# 18F4520SCH_-_Copy.net
KiCad netlist of a schematic drawn in Altium Designer
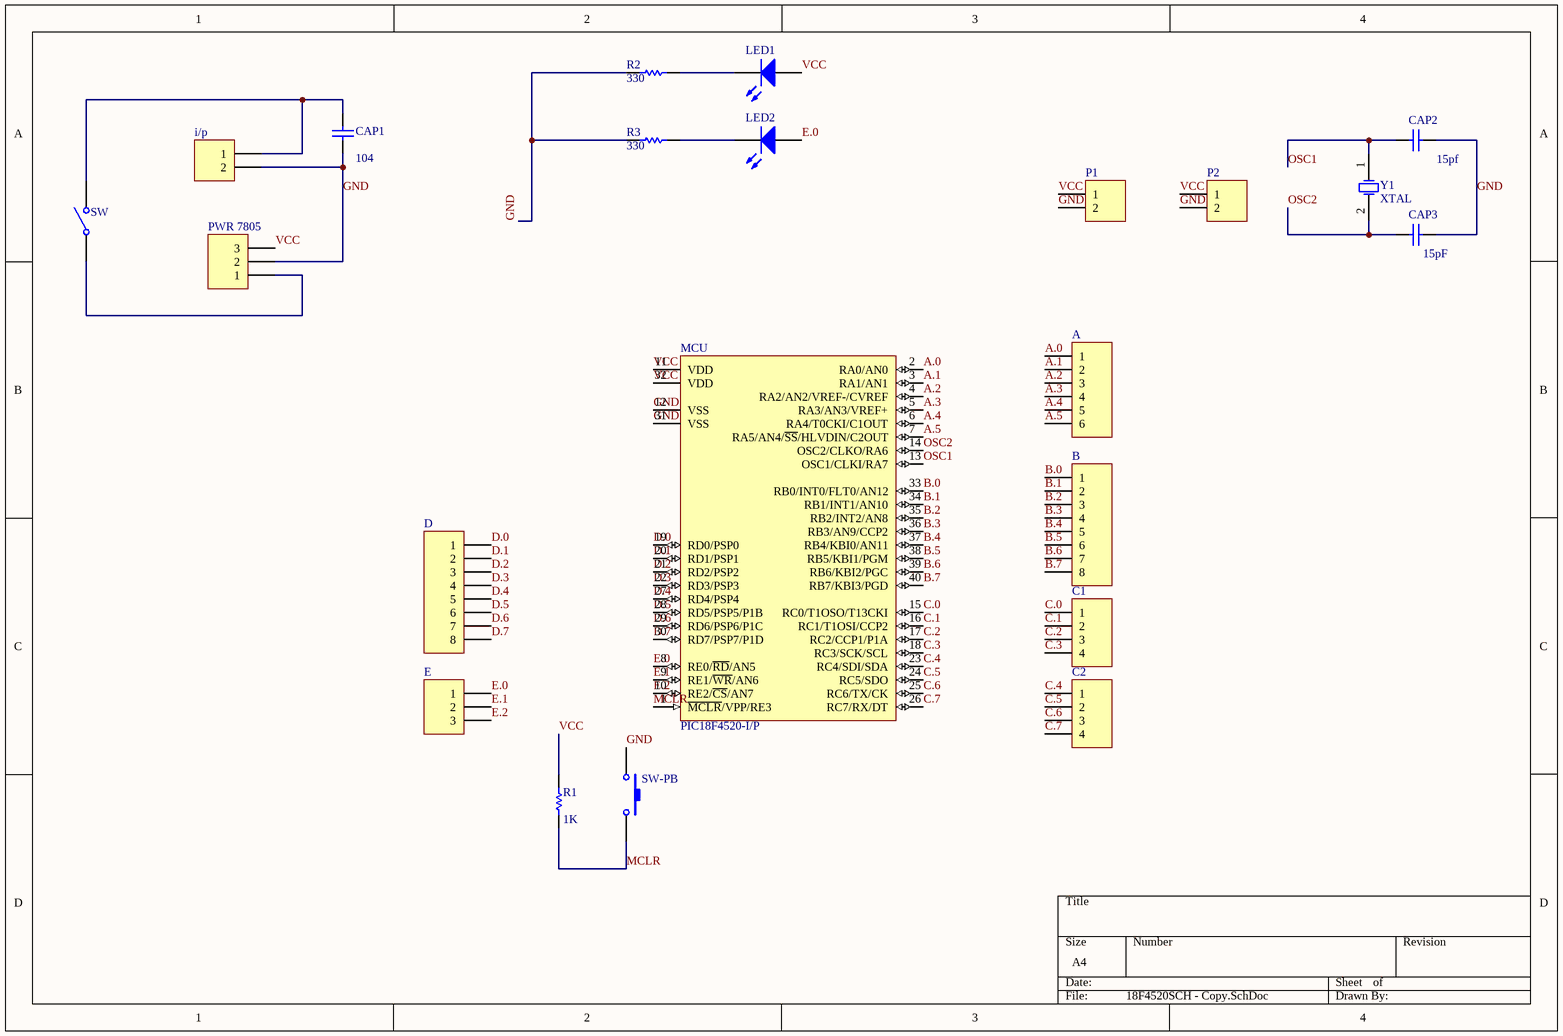
[diagram p0: 18F4520SCH - Copy.SchDoc]

(export (version "E")
  (design (tool "Eeschema 10.0.6"))
  (components
    (comp (ref "A")
      (value "Header 6")
      (footprint "HDR1X6")
      (description "Header, 6-Pin")
      (fields (field (name "PUBLISHER") "Altium Limited"))
      (libsource (lib "Miscellaneous Connectors") (part "Header 6"))
    )
    (comp (ref "B")
      (value "Header 8")
      (footprint "HDR1X8")
      (description "Header, 8-Pin")
      (fields (field (name "PUBLISHER") "Altium Limited"))
      (libsource (lib "") (part "Header 8_1"))
    )
    (comp (ref "C1")
      (value "Header 4")
      (footprint "HDR1X4")
      (description "Header, 4-Pin")
      (fields (field (name "PUBLISHER") "Altium Limited"))
      (libsource (lib "Miscellaneous Connectors") (part "Header 4"))
    )
    (comp (ref "C2")
      (value "Header 4")
      (footprint "HDR1X4")
      (description "Header, 4-Pin")
      (fields (field (name "PUBLISHER") "Altium Limited"))
      (libsource (lib "Miscellaneous Connectors") (part "Header 4"))
    )
    (comp (ref "CAP1")
      (value "104")
      (footprint "Miscellaneous Connectors:HDR1X2")
      (description "Capacitor")
      (fields (field (name "Comment") "Cap") (field (name "PUBLISHER") "Altium Limited"))
      (libsource (lib "Miscellaneous Devices") (part "Cap"))
    )
    (comp (ref "CAP2")
      (value "15pf")
      (footprint "Miscellaneous Connectors:HDR1X2")
      (description "Capacitor")
      (fields (field (name "Comment") "Cap") (field (name "PUBLISHER") "Altium Limited"))
      (libsource (lib "Miscellaneous Devices") (part "Cap"))
    )
    (comp (ref "CAP3")
      (value "15pF")
      (footprint "Miscellaneous Connectors:HDR1X2")
      (description "Capacitor")
      (fields (field (name "Comment") "Cap") (field (name "PUBLISHER") "Altium Limited"))
      (libsource (lib "Miscellaneous Devices") (part "Cap"))
    )
    (comp (ref "D")
      (value "Header 8")
      (footprint "HDR1X8")
      (description "Header, 8-Pin")
      (fields (field (name "PUBLISHER") "Altium Limited"))
      (libsource (lib "Miscellaneous Connectors") (part "Header 8"))
    )
    (comp (ref "E")
      (value "Header 3")
      (footprint "HDR1X3")
      (description "Header, 3-Pin")
      (fields (field (name "PUBLISHER") "Altium Limited"))
      (libsource (lib "Miscellaneous Connectors") (part "Header 3"))
    )
    (comp (ref "i/p")
      (value "Header 2")
      (footprint "HDR1X2")
      (description "Header, 2-Pin")
      (fields (field (name "PUBLISHER") "Altium Limited"))
      (libsource (lib "Miscellaneous Connectors") (part "Header 2"))
    )
    (comp (ref "LED1")
      (value "LED2")
      (footprint "Miscellaneous Connectors:HDR1X2")
      (description "Typical RED, GREEN, YELLOW, AMBER GaAs LED")
      (fields (field (name "PUBLISHER") "Altium Limited"))
      (libsource (lib "Miscellaneous Devices") (part "LED2"))
    )
    (comp (ref "LED2")
      (value "LED2")
      (footprint "Miscellaneous Connectors:HDR1X2")
      (description "Typical RED, GREEN, YELLOW, AMBER GaAs LED")
      (fields (field (name "PUBLISHER") "Altium Limited"))
      (libsource (lib "Miscellaneous Devices") (part "LED2"))
    )
    (comp (ref "MCU")
      (value "PIC18F4520-I/P")
      (footprint "Microchip Microcontroller 8-Bit PIC16:PDIP600-P40")
      (fields (field (name "PUBLISHER") "Altium Limited"))
      (libsource (lib "Microchip Microcontroller 8-Bit PIC18") (part "PIC18F4520-I/P"))
    )
    (comp (ref "P1")
      (value "Header 2")
      (footprint "HDR1X2")
      (description "Header, 2-Pin")
      (fields (field (name "PUBLISHER") "Altium Limited"))
      (libsource (lib "") (part "Header 2_1"))
    )
    (comp (ref "P2")
      (value "Header 2")
      (footprint "HDR1X2")
      (description "Header, 2-Pin")
      (fields (field (name "PUBLISHER") "Altium Limited"))
      (libsource (lib "") (part "Header 2_1"))
    )
    (comp (ref "PWR 7805")
      (value "Header 3")
      (footprint "HDR1X3")
      (description "Header, 3-Pin")
      (fields (field (name "PUBLISHER") "Altium Limited"))
      (libsource (lib "") (part "Header 3_1"))
    )
    (comp (ref "R1")
      (value "1K")
      (footprint "AXIAL-0.3")
      (description "Resistor")
      (fields (field (name "Comment") "Res1") (field (name "PUBLISHER") "Altium Limited"))
      (libsource (lib "Miscellaneous Devices") (part "Res1"))
    )
    (comp (ref "R2")
      (value "330")
      (footprint "AXIAL-0.3")
      (description "Resistor")
      (fields (field (name "Comment") "Res1") (field (name "PUBLISHER") "Altium Limited"))
      (libsource (lib "Miscellaneous Devices") (part "Res1"))
    )
    (comp (ref "R3")
      (value "330")
      (footprint "AXIAL-0.3")
      (description "Resistor")
      (fields (field (name "Comment") "Res1") (field (name "PUBLISHER") "Altium Limited"))
      (libsource (lib "Miscellaneous Devices") (part "Res1"))
    )
    (comp (ref "SW")
      (value "SW-SPST")
      (footprint "SPST-2")
      (description "Single-Pole, Single-Throw Switch")
      (fields (field (name "PUBLISHER") "Altium Limited"))
      (libsource (lib "Miscellaneous Devices") (part "SW-SPST"))
    )
    (comp (ref "SW-PB")
      (value "SW-PB")
      (footprint "SPST-2")
      (description "Switch")
      (fields (field (name "PUBLISHER") "Altium Limited"))
      (libsource (lib "Miscellaneous Devices") (part "SW-PB"))
    )
    (comp (ref "Y1")
      (value "XTAL")
      (footprint "R38")
      (description "Crystal Oscillator")
      (fields (field (name "PUBLISHER") "Altium Limited"))
      (libsource (lib "Miscellaneous Devices") (part "XTAL"))
    )
  )
  (nets
    (net (code "1") (name "/A.0") (class "Default")
      (node (ref "A") (pin "1") (pinfunction "1_1") (pintype "passive"))
      (node (ref "MCU") (pin "2") (pinfunction "RA0/AN0_2") (pintype "bidirectional"))
    )
    (net (code "2") (name "/A.1") (class "Default")
      (node (ref "A") (pin "2") (pinfunction "2_2") (pintype "passive"))
      (node (ref "MCU") (pin "3") (pinfunction "RA1/AN1_3") (pintype "bidirectional"))
    )
    (net (code "3") (name "/A.2") (class "Default")
      (node (ref "A") (pin "3") (pinfunction "3_3") (pintype "passive"))
      (node (ref "MCU") (pin "4") (pinfunction "RA2/AN2/VREF-/CVREF_4") (pintype "bidirectional"))
    )
    (net (code "4") (name "/A.3") (class "Default")
      (node (ref "A") (pin "4") (pinfunction "4_4") (pintype "passive"))
      (node (ref "MCU") (pin "5") (pinfunction "RA3/AN3/VREF+_5") (pintype "bidirectional"))
    )
    (net (code "5") (name "/A.4") (class "Default")
      (node (ref "A") (pin "5") (pinfunction "5_5") (pintype "passive"))
      (node (ref "MCU") (pin "6") (pinfunction "RA4/T0CKI/C1OUT_6") (pintype "bidirectional"))
    )
    (net (code "6") (name "/A.5") (class "Default")
      (node (ref "A") (pin "6") (pinfunction "6_6") (pintype "passive"))
      (node (ref "MCU") (pin "7") (pinfunction "RA5/AN4/~{SS}/HLVDIN/C2OUT_7") (pintype "bidirectional"))
    )
    (net (code "7") (name "/B.0") (class "Default")
      (node (ref "B") (pin "1") (pinfunction "1_1") (pintype "passive"))
      (node (ref "MCU") (pin "33") (pinfunction "RB0/INT0/FLT0/AN12_33") (pintype "bidirectional"))
    )
    (net (code "8") (name "/B.1") (class "Default")
      (node (ref "B") (pin "2") (pinfunction "2_2") (pintype "passive"))
      (node (ref "MCU") (pin "34") (pinfunction "RB1/INT1/AN10_34") (pintype "bidirectional"))
    )
    (net (code "9") (name "/B.2") (class "Default")
      (node (ref "B") (pin "3") (pinfunction "3_3") (pintype "passive"))
      (node (ref "MCU") (pin "35") (pinfunction "RB2/INT2/AN8_35") (pintype "bidirectional"))
    )
    (net (code "10") (name "/B.3") (class "Default")
      (node (ref "B") (pin "4") (pinfunction "4_4") (pintype "passive"))
      (node (ref "MCU") (pin "36") (pinfunction "RB3/AN9/CCP2_36") (pintype "bidirectional"))
    )
    (net (code "11") (name "/B.4") (class "Default")
      (node (ref "B") (pin "5") (pinfunction "5_5") (pintype "passive"))
      (node (ref "MCU") (pin "37") (pinfunction "RB4/KBI0/AN11_37") (pintype "bidirectional"))
    )
    (net (code "12") (name "/B.5") (class "Default")
      (node (ref "B") (pin "6") (pinfunction "6_6") (pintype "passive"))
      (node (ref "MCU") (pin "38") (pinfunction "RB5/KBI1/PGM_38") (pintype "bidirectional"))
    )
    (net (code "13") (name "/B.6") (class "Default")
      (node (ref "B") (pin "7") (pinfunction "7_7") (pintype "passive"))
      (node (ref "MCU") (pin "39") (pinfunction "RB6/KBI2/PGC_39") (pintype "bidirectional"))
    )
    (net (code "14") (name "/B.7") (class "Default")
      (node (ref "B") (pin "8") (pinfunction "8_8") (pintype "passive"))
      (node (ref "MCU") (pin "40") (pinfunction "RB7/KBI3/PGD_40") (pintype "bidirectional"))
    )
    (net (code "15") (name "/C.0") (class "Default")
      (node (ref "C1") (pin "1") (pinfunction "1_1") (pintype "passive"))
      (node (ref "MCU") (pin "15") (pinfunction "RC0/T1OSO/T13CKI_15") (pintype "bidirectional"))
    )
    (net (code "16") (name "/C.1") (class "Default")
      (node (ref "C1") (pin "2") (pinfunction "2_2") (pintype "passive"))
      (node (ref "MCU") (pin "16") (pinfunction "RC1/T1OSI/CCP2_16") (pintype "bidirectional"))
    )
    (net (code "17") (name "/C.2") (class "Default")
      (node (ref "C1") (pin "3") (pinfunction "3_3") (pintype "passive"))
      (node (ref "MCU") (pin "17") (pinfunction "RC2/CCP1/P1A_17") (pintype "bidirectional"))
    )
    (net (code "18") (name "/C.3") (class "Default")
      (node (ref "C1") (pin "4") (pinfunction "4_4") (pintype "passive"))
      (node (ref "MCU") (pin "18") (pinfunction "RC3/SCK/SCL_18") (pintype "bidirectional"))
    )
    (net (code "19") (name "/C.4") (class "Default")
      (node (ref "C2") (pin "1") (pinfunction "1_1") (pintype "passive"))
      (node (ref "MCU") (pin "23") (pinfunction "RC4/SDI/SDA_23") (pintype "bidirectional"))
    )
    (net (code "20") (name "/C.5") (class "Default")
      (node (ref "C2") (pin "2") (pinfunction "2_2") (pintype "passive"))
      (node (ref "MCU") (pin "24") (pinfunction "RC5/SDO_24") (pintype "bidirectional"))
    )
    (net (code "21") (name "/C.6") (class "Default")
      (node (ref "C2") (pin "3") (pinfunction "3_3") (pintype "passive"))
      (node (ref "MCU") (pin "25") (pinfunction "RC6/TX/CK_25") (pintype "bidirectional"))
    )
    (net (code "22") (name "/C.7") (class "Default")
      (node (ref "C2") (pin "4") (pinfunction "4_4") (pintype "passive"))
      (node (ref "MCU") (pin "26") (pinfunction "RC7/RX/DT_26") (pintype "bidirectional"))
    )
    (net (code "23") (name "/D.0") (class "Default")
      (node (ref "D") (pin "1") (pinfunction "1_1") (pintype "passive"))
      (node (ref "MCU") (pin "19") (pinfunction "RD0/PSP0_19") (pintype "bidirectional"))
    )
    (net (code "24") (name "/D.1") (class "Default")
      (node (ref "D") (pin "2") (pinfunction "2_2") (pintype "passive"))
      (node (ref "MCU") (pin "20") (pinfunction "RD1/PSP1_20") (pintype "bidirectional"))
    )
    (net (code "25") (name "/D.2") (class "Default")
      (node (ref "D") (pin "3") (pinfunction "3_3") (pintype "passive"))
      (node (ref "MCU") (pin "21") (pinfunction "RD2/PSP2_21") (pintype "bidirectional"))
    )
    (net (code "26") (name "/D.3") (class "Default")
      (node (ref "D") (pin "4") (pinfunction "4_4") (pintype "passive"))
      (node (ref "MCU") (pin "22") (pinfunction "RD3/PSP3_22") (pintype "bidirectional"))
    )
    (net (code "27") (name "/D.4") (class "Default")
      (node (ref "D") (pin "5") (pinfunction "5_5") (pintype "passive"))
      (node (ref "MCU") (pin "27") (pinfunction "RD4/PSP4_27") (pintype "bidirectional"))
    )
    (net (code "28") (name "/D.5") (class "Default")
      (node (ref "D") (pin "6") (pinfunction "6_6") (pintype "passive"))
      (node (ref "MCU") (pin "28") (pinfunction "RD5/PSP5/P1B_28") (pintype "bidirectional"))
    )
    (net (code "29") (name "/D.6") (class "Default")
      (node (ref "D") (pin "7") (pinfunction "7_7") (pintype "passive"))
      (node (ref "MCU") (pin "29") (pinfunction "RD6/PSP6/P1C_29") (pintype "bidirectional"))
    )
    (net (code "30") (name "/D.7") (class "Default")
      (node (ref "D") (pin "8") (pinfunction "8_8") (pintype "passive"))
      (node (ref "MCU") (pin "30") (pinfunction "RD7/PSP7/P1D_30") (pintype "bidirectional"))
    )
    (net (code "31") (name "/E.0") (class "Default")
      (node (ref "E") (pin "1") (pinfunction "1_1") (pintype "passive"))
      (node (ref "LED2") (pin "1") (pinfunction "A_1") (pintype "passive"))
      (node (ref "MCU") (pin "8") (pinfunction "RE0/~{RD}/AN5_8") (pintype "bidirectional"))
    )
    (net (code "32") (name "/E.1") (class "Default")
      (node (ref "E") (pin "2") (pinfunction "2_2") (pintype "passive"))
      (node (ref "MCU") (pin "9") (pinfunction "RE1/~{WR}/AN6_9") (pintype "bidirectional"))
    )
    (net (code "33") (name "/E.2") (class "Default")
      (node (ref "E") (pin "3") (pinfunction "3_3") (pintype "passive"))
      (node (ref "MCU") (pin "10") (pinfunction "RE2/~{CS}/AN7_10") (pintype "bidirectional"))
    )
    (net (code "34") (name "/GND") (class "Default")
      (node (ref "CAP1") (pin "1") (pinfunction "1_1") (pintype "passive"))
      (node (ref "CAP2") (pin "2") (pinfunction "2_2") (pintype "passive"))
      (node (ref "CAP3") (pin "2") (pinfunction "2_2") (pintype "passive"))
      (node (ref "MCU") (pin "12") (pinfunction "VSS_12") (pintype "power_in"))
      (node (ref "MCU") (pin "31") (pinfunction "VSS_31") (pintype "power_in"))
      (node (ref "P1") (pin "2") (pinfunction "2_2") (pintype "passive"))
      (node (ref "P2") (pin "2") (pinfunction "2_2") (pintype "passive"))
      (node (ref "PWR 7805") (pin "2") (pinfunction "2_2") (pintype "passive"))
      (node (ref "R2") (pin "1") (pinfunction "1_1") (pintype "passive"))
      (node (ref "R3") (pin "1") (pinfunction "1_1") (pintype "passive"))
      (node (ref "SW-PB") (pin "1") (pinfunction "1_1") (pintype "passive"))
      (node (ref "i/p") (pin "2") (pinfunction "2_2") (pintype "passive"))
    )
    (net (code "35") (name "/MCLR") (class "Default")
      (node (ref "MCU") (pin "1") (pinfunction "~{MCLR}/VPP/RE3_1") (pintype "input"))
      (node (ref "R1") (pin "1") (pinfunction "1_1") (pintype "passive"))
      (node (ref "SW-PB") (pin "2") (pinfunction "2_2") (pintype "passive"))
    )
    (net (code "36") (name "/OSC1") (class "Default")
      (node (ref "CAP2") (pin "1") (pinfunction "1_1") (pintype "passive"))
      (node (ref "MCU") (pin "13") (pinfunction "OSC1/CLKI/RA7_13") (pintype "bidirectional"))
      (node (ref "Y1") (pin "1") (pinfunction "OSC1_1") (pintype "passive"))
    )
    (net (code "37") (name "/OSC2") (class "Default")
      (node (ref "CAP3") (pin "1") (pinfunction "1_1") (pintype "passive"))
      (node (ref "MCU") (pin "14") (pinfunction "OSC2/CLKO/RA6_14") (pintype "bidirectional"))
      (node (ref "Y1") (pin "2") (pinfunction "OSC2_2") (pintype "passive"))
    )
    (net (code "38") (name "/VCC") (class "Default")
      (node (ref "LED1") (pin "1") (pinfunction "A_1") (pintype "passive"))
      (node (ref "MCU") (pin "11") (pinfunction "VDD_11") (pintype "power_in"))
      (node (ref "MCU") (pin "32") (pinfunction "VDD_32") (pintype "power_in"))
      (node (ref "P1") (pin "1") (pinfunction "1_1") (pintype "passive"))
      (node (ref "P2") (pin "1") (pinfunction "1_1") (pintype "passive"))
      (node (ref "PWR 7805") (pin "3") (pinfunction "3_3") (pintype "passive"))
      (node (ref "R1") (pin "2") (pinfunction "2_2") (pintype "passive"))
    )
    (net (code "39") (name "Net-(LED1-K)") (class "Default")
      (node (ref "LED1") (pin "2") (pinfunction "K_2") (pintype "passive"))
      (node (ref "R2") (pin "2") (pinfunction "2_2") (pintype "passive"))
    )
    (net (code "40") (name "Net-(LED2-K)") (class "Default")
      (node (ref "LED2") (pin "2") (pinfunction "K_2") (pintype "passive"))
      (node (ref "R3") (pin "2") (pinfunction "2_2") (pintype "passive"))
    )
    (net (code "41") (name "Net-(SW-COMMON)") (class "Default")
      (node (ref "PWR 7805") (pin "1") (pinfunction "1_1") (pintype "passive"))
      (node (ref "SW") (pin "1") (pinfunction "COMMON_1") (pintype "passive"))
    )
    (net (code "42") (name "Net-(SW-NO)") (class "Default")
      (node (ref "CAP1") (pin "2") (pinfunction "2_2") (pintype "passive"))
      (node (ref "SW") (pin "2") (pinfunction "NO_2") (pintype "passive"))
      (node (ref "i/p") (pin "1") (pinfunction "1_1") (pintype "passive"))
    )
  )
)
